# untitled.net
KiCad netlist of a schematic drawn in EAGLE
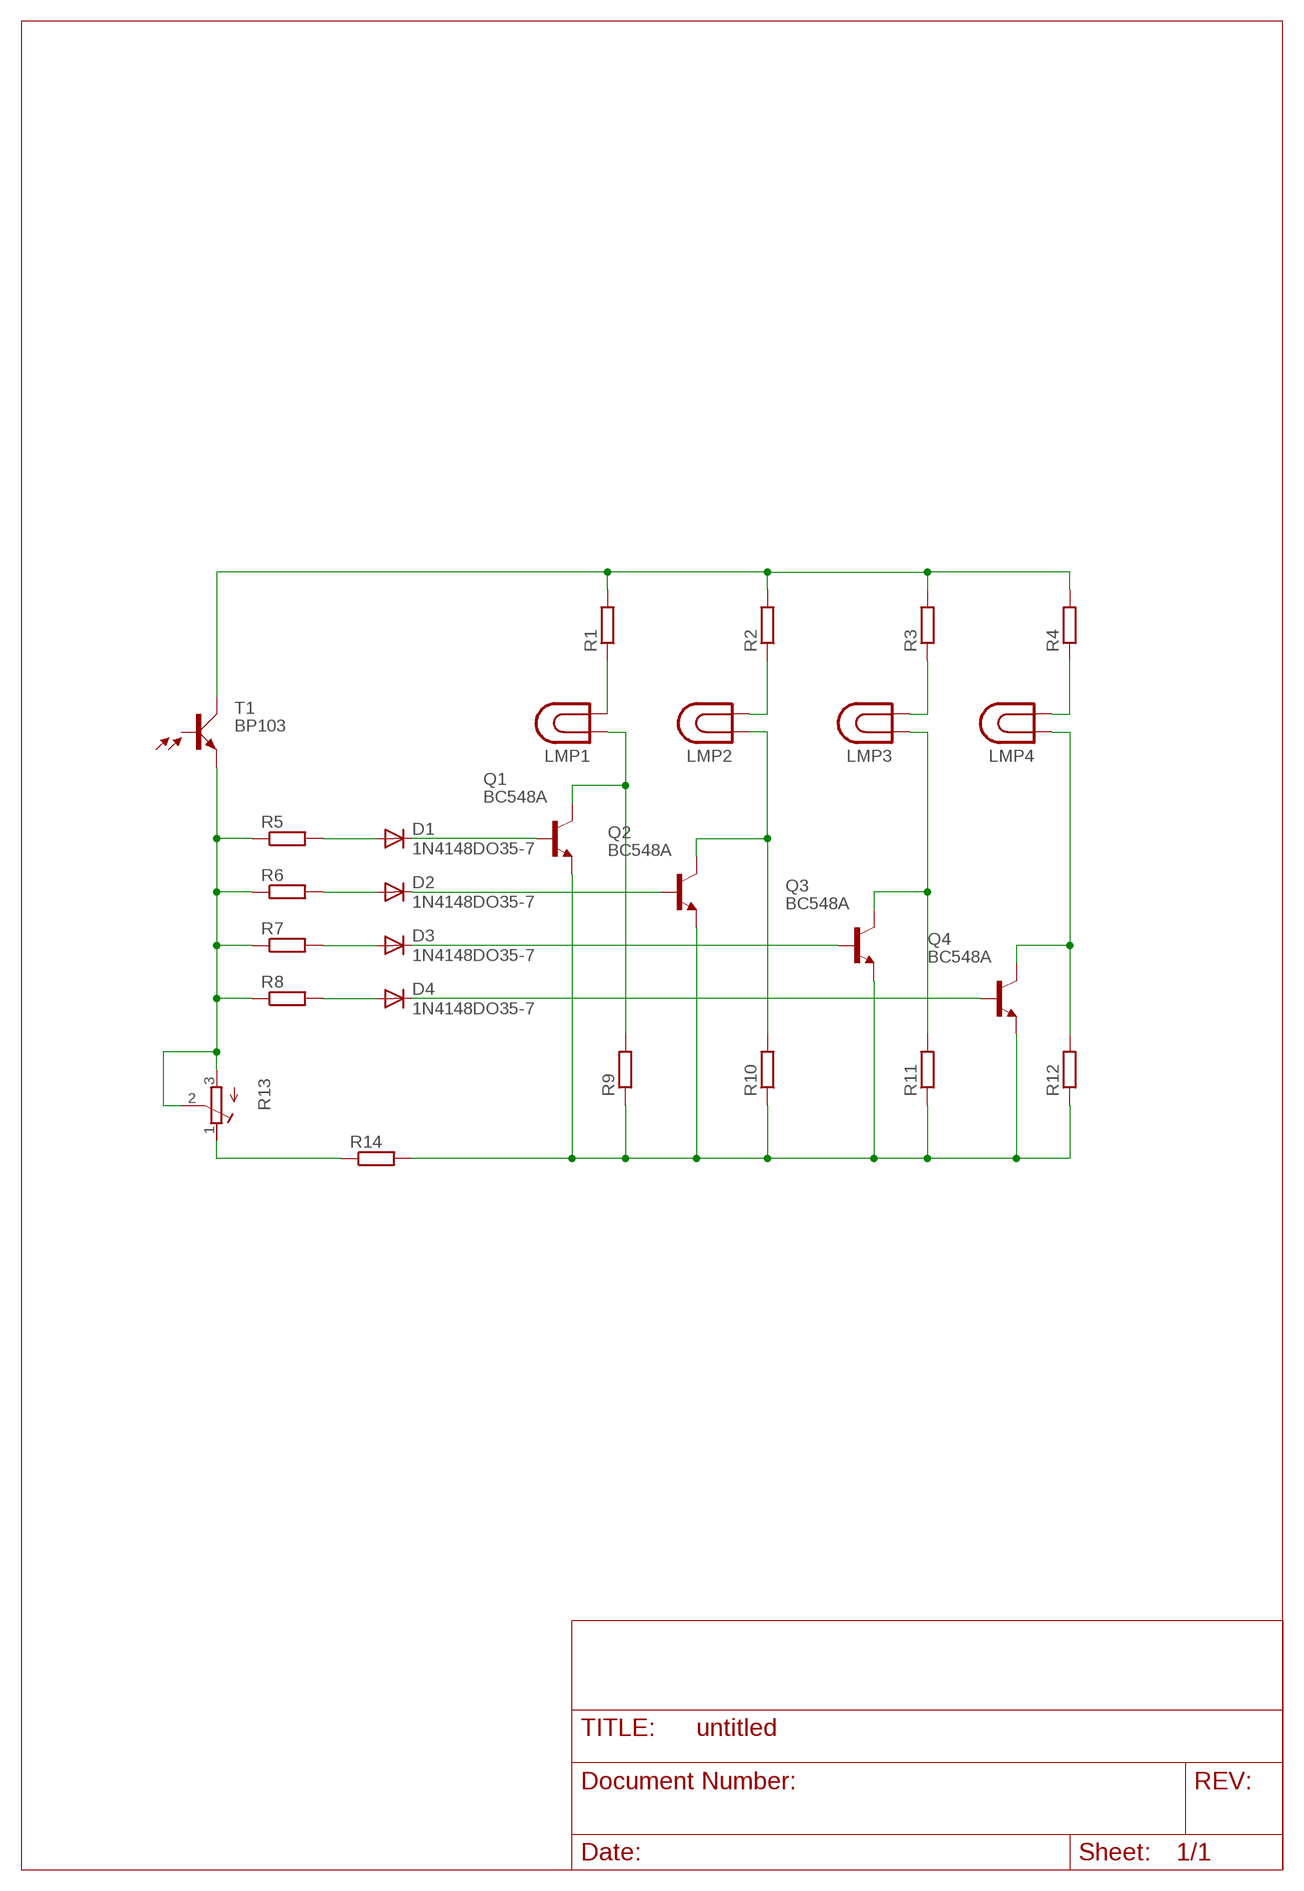
[diagram p0: schematic, sheet 1]

(export (version "E")
  (design (tool "Eeschema 10.0.6"))
  (components
    (comp (ref "D1")
      (value "1N4148DO35-7")
      (footprint "eagle-import:DO35-7")
      (libsource (lib "eagle-import") (part "1N4148DO35-7"))
    )
    (comp (ref "D2")
      (value "1N4148DO35-7")
      (footprint "eagle-import:DO35-7")
      (libsource (lib "eagle-import") (part "1N4148DO35-7"))
    )
    (comp (ref "D3")
      (value "1N4148DO35-7")
      (footprint "eagle-import:DO35-7")
      (libsource (lib "eagle-import") (part "1N4148DO35-7"))
    )
    (comp (ref "D4")
      (value "1N4148DO35-7")
      (footprint "eagle-import:DO35-7")
      (libsource (lib "eagle-import") (part "1N4148DO35-7"))
    )
    (comp (ref "LMP1")
      (value "LAMP")
      (footprint "eagle-import:LDH-5R")
      (libsource (lib "eagle-import") (part "LAMP"))
    )
    (comp (ref "LMP2")
      (value "LAMP")
      (footprint "eagle-import:LDH-5R")
      (libsource (lib "eagle-import") (part "LAMP"))
    )
    (comp (ref "LMP3")
      (value "LAMP")
      (footprint "eagle-import:LDH-5R")
      (libsource (lib "eagle-import") (part "LAMP"))
    )
    (comp (ref "LMP4")
      (value "LAMP")
      (footprint "eagle-import:LDH-5R")
      (libsource (lib "eagle-import") (part "LAMP"))
    )
    (comp (ref "Q1")
      (value "BC548A")
      (footprint "eagle-import:TO92-EBC")
      (libsource (lib "eagle-import") (part "BC548A"))
    )
    (comp (ref "Q2")
      (value "BC548A")
      (footprint "eagle-import:TO92-EBC")
      (libsource (lib "eagle-import") (part "BC548A"))
    )
    (comp (ref "Q3")
      (value "BC548A")
      (footprint "eagle-import:TO92-EBC")
      (libsource (lib "eagle-import") (part "BC548A"))
    )
    (comp (ref "Q4")
      (value "BC548A")
      (footprint "eagle-import:TO92-EBC")
      (libsource (lib "eagle-import") (part "BC548A"))
    )
    (comp (ref "R1")
      (value "R-EU_0207/10")
      (footprint "eagle-import:0207_10")
      (libsource (lib "eagle-import") (part "R-EU_0207/10"))
    )
    (comp (ref "R2")
      (value "R-EU_0207/10")
      (footprint "eagle-import:0207_10")
      (libsource (lib "eagle-import") (part "R-EU_0207/10"))
    )
    (comp (ref "R3")
      (value "R-EU_0207/10")
      (footprint "eagle-import:0207_10")
      (libsource (lib "eagle-import") (part "R-EU_0207/10"))
    )
    (comp (ref "R4")
      (value "R-EU_0207/10")
      (footprint "eagle-import:0207_10")
      (libsource (lib "eagle-import") (part "R-EU_0207/10"))
    )
    (comp (ref "R5")
      (value "R-EU_0207/10")
      (footprint "eagle-import:0207_10")
      (libsource (lib "eagle-import") (part "R-EU_0207/10"))
    )
    (comp (ref "R6")
      (value "R-EU_0207/10")
      (footprint "eagle-import:0207_10")
      (libsource (lib "eagle-import") (part "R-EU_0207/10"))
    )
    (comp (ref "R7")
      (value "R-EU_0207/10")
      (footprint "eagle-import:0207_10")
      (libsource (lib "eagle-import") (part "R-EU_0207/10"))
    )
    (comp (ref "R8")
      (value "R-EU_0207/10")
      (footprint "eagle-import:0207_10")
      (libsource (lib "eagle-import") (part "R-EU_0207/10"))
    )
    (comp (ref "R9")
      (value "R-EU_0207/10")
      (footprint "eagle-import:0207_10")
      (libsource (lib "eagle-import") (part "R-EU_0207/10"))
    )
    (comp (ref "R10")
      (value "R-EU_0207/10")
      (footprint "eagle-import:0207_10")
      (libsource (lib "eagle-import") (part "R-EU_0207/10"))
    )
    (comp (ref "R11")
      (value "R-EU_0207/10")
      (footprint "eagle-import:0207_10")
      (libsource (lib "eagle-import") (part "R-EU_0207/10"))
    )
    (comp (ref "R12")
      (value "R-EU_0207/10")
      (footprint "eagle-import:0207_10")
      (libsource (lib "eagle-import") (part "R-EU_0207/10"))
    )
    (comp (ref "R13")
      (value "R-TRIMM43P")
      (footprint "eagle-import:RTRIM43P")
      (libsource (lib "eagle-import") (part "R-TRIMM43P"))
    )
    (comp (ref "R14")
      (value "R-EU_0207/10")
      (footprint "eagle-import:0207_10")
      (libsource (lib "eagle-import") (part "R-EU_0207/10"))
    )
    (comp (ref "T1")
      (value "BP103")
      (footprint "eagle-import:BP103")
      (libsource (lib "eagle-import") (part "BP103"))
    )
  )
  (nets
    (net (code "1") (name "Net-(D1-PadA)") (class "Default")
      (node (ref "D1") (pin "A") (pinfunction "A_A") (pintype "passive"))
      (node (ref "R5") (pin "2") (pinfunction "2_2") (pintype "passive"))
    )
    (net (code "2") (name "Net-(D1-PadC)") (class "Default")
      (node (ref "D1") (pin "C") (pinfunction "C_C") (pintype "passive"))
      (node (ref "Q1") (pin "B") (pinfunction "B_B") (pintype "passive"))
    )
    (net (code "3") (name "Net-(D2-PadA)") (class "Default")
      (node (ref "D2") (pin "A") (pinfunction "A_A") (pintype "passive"))
      (node (ref "R6") (pin "2") (pinfunction "2_2") (pintype "passive"))
    )
    (net (code "4") (name "Net-(D2-PadC)") (class "Default")
      (node (ref "D2") (pin "C") (pinfunction "C_C") (pintype "passive"))
      (node (ref "Q2") (pin "B") (pinfunction "B_B") (pintype "passive"))
    )
    (net (code "5") (name "Net-(D3-PadA)") (class "Default")
      (node (ref "D3") (pin "A") (pinfunction "A_A") (pintype "passive"))
      (node (ref "R7") (pin "2") (pinfunction "2_2") (pintype "passive"))
    )
    (net (code "6") (name "Net-(D3-PadC)") (class "Default")
      (node (ref "D3") (pin "C") (pinfunction "C_C") (pintype "passive"))
      (node (ref "Q3") (pin "B") (pinfunction "B_B") (pintype "passive"))
    )
    (net (code "7") (name "Net-(D4-PadA)") (class "Default")
      (node (ref "D4") (pin "A") (pinfunction "A_A") (pintype "passive"))
      (node (ref "R8") (pin "2") (pinfunction "2_2") (pintype "passive"))
    )
    (net (code "8") (name "Net-(D4-PadC)") (class "Default")
      (node (ref "D4") (pin "C") (pinfunction "C_C") (pintype "passive"))
      (node (ref "Q4") (pin "B") (pinfunction "B_B") (pintype "passive"))
    )
    (net (code "9") (name "Net-(LMP1-Pad1)") (class "Default")
      (node (ref "LMP1") (pin "1") (pinfunction "1_1") (pintype "passive"))
      (node (ref "Q1") (pin "C") (pinfunction "C_C") (pintype "passive"))
      (node (ref "R9") (pin "2") (pinfunction "2_2") (pintype "passive"))
    )
    (net (code "10") (name "Net-(LMP1-Pad2)") (class "Default")
      (node (ref "LMP1") (pin "2") (pinfunction "2_2") (pintype "passive"))
      (node (ref "R1") (pin "1") (pinfunction "1_1") (pintype "passive"))
    )
    (net (code "11") (name "Net-(LMP2-Pad1)") (class "Default")
      (node (ref "LMP2") (pin "1") (pinfunction "1_1") (pintype "passive"))
      (node (ref "Q2") (pin "C") (pinfunction "C_C") (pintype "passive"))
      (node (ref "R10") (pin "2") (pinfunction "2_2") (pintype "passive"))
    )
    (net (code "12") (name "Net-(LMP2-Pad2)") (class "Default")
      (node (ref "LMP2") (pin "2") (pinfunction "2_2") (pintype "passive"))
      (node (ref "R2") (pin "1") (pinfunction "1_1") (pintype "passive"))
    )
    (net (code "13") (name "Net-(LMP3-Pad1)") (class "Default")
      (node (ref "LMP3") (pin "1") (pinfunction "1_1") (pintype "passive"))
      (node (ref "Q3") (pin "C") (pinfunction "C_C") (pintype "passive"))
      (node (ref "R11") (pin "2") (pinfunction "2_2") (pintype "passive"))
    )
    (net (code "14") (name "Net-(LMP3-Pad2)") (class "Default")
      (node (ref "LMP3") (pin "2") (pinfunction "2_2") (pintype "passive"))
      (node (ref "R3") (pin "1") (pinfunction "1_1") (pintype "passive"))
    )
    (net (code "15") (name "Net-(LMP4-Pad1)") (class "Default")
      (node (ref "LMP4") (pin "1") (pinfunction "1_1") (pintype "passive"))
      (node (ref "Q4") (pin "C") (pinfunction "C_C") (pintype "passive"))
      (node (ref "R12") (pin "2") (pinfunction "2_2") (pintype "passive"))
    )
    (net (code "16") (name "Net-(LMP4-Pad2)") (class "Default")
      (node (ref "LMP4") (pin "2") (pinfunction "2_2") (pintype "passive"))
      (node (ref "R4") (pin "1") (pinfunction "1_1") (pintype "passive"))
    )
    (net (code "17") (name "Net-(Q1-PadE)") (class "Default")
      (node (ref "Q1") (pin "E") (pinfunction "E_E") (pintype "passive"))
      (node (ref "Q2") (pin "E") (pinfunction "E_E") (pintype "passive"))
      (node (ref "Q3") (pin "E") (pinfunction "E_E") (pintype "passive"))
      (node (ref "Q4") (pin "E") (pinfunction "E_E") (pintype "passive"))
      (node (ref "R10") (pin "1") (pinfunction "1_1") (pintype "passive"))
      (node (ref "R11") (pin "1") (pinfunction "1_1") (pintype "passive"))
      (node (ref "R12") (pin "1") (pinfunction "1_1") (pintype "passive"))
      (node (ref "R14") (pin "2") (pinfunction "2_2") (pintype "passive"))
      (node (ref "R9") (pin "1") (pinfunction "1_1") (pintype "passive"))
    )
    (net (code "18") (name "Net-(R1-Pad2)") (class "Default")
      (node (ref "R1") (pin "2") (pinfunction "2_2") (pintype "passive"))
      (node (ref "R2") (pin "2") (pinfunction "2_2") (pintype "passive"))
      (node (ref "R3") (pin "2") (pinfunction "2_2") (pintype "passive"))
      (node (ref "R4") (pin "2") (pinfunction "2_2") (pintype "passive"))
      (node (ref "T1") (pin "C") (pinfunction "C_C") (pintype "passive"))
    )
    (net (code "19") (name "Net-(R13-A)") (class "Default")
      (node (ref "R13") (pin "2") (pinfunction "S_2") (pintype "passive"))
      (node (ref "R13") (pin "3") (pinfunction "A_3") (pintype "passive"))
      (node (ref "R5") (pin "1") (pinfunction "1_1") (pintype "passive"))
      (node (ref "R6") (pin "1") (pinfunction "1_1") (pintype "passive"))
      (node (ref "R7") (pin "1") (pinfunction "1_1") (pintype "passive"))
      (node (ref "R8") (pin "1") (pinfunction "1_1") (pintype "passive"))
      (node (ref "T1") (pin "E") (pinfunction "E_E") (pintype "passive"))
    )
    (net (code "20") (name "Net-(R13-E)") (class "Default")
      (node (ref "R13") (pin "1") (pinfunction "E_1") (pintype "passive"))
      (node (ref "R14") (pin "1") (pinfunction "1_1") (pintype "passive"))
    )
    (net (code "21") (name "unconnected-(T1-PadB)") (class "Default")
      (node (ref "T1") (pin "B") (pinfunction "B_B") (pintype "passive"))
    )
  )
)
